# Mouse_STM32F401_DB9.net
KiCad netlist of a schematic drawn in EAGLE
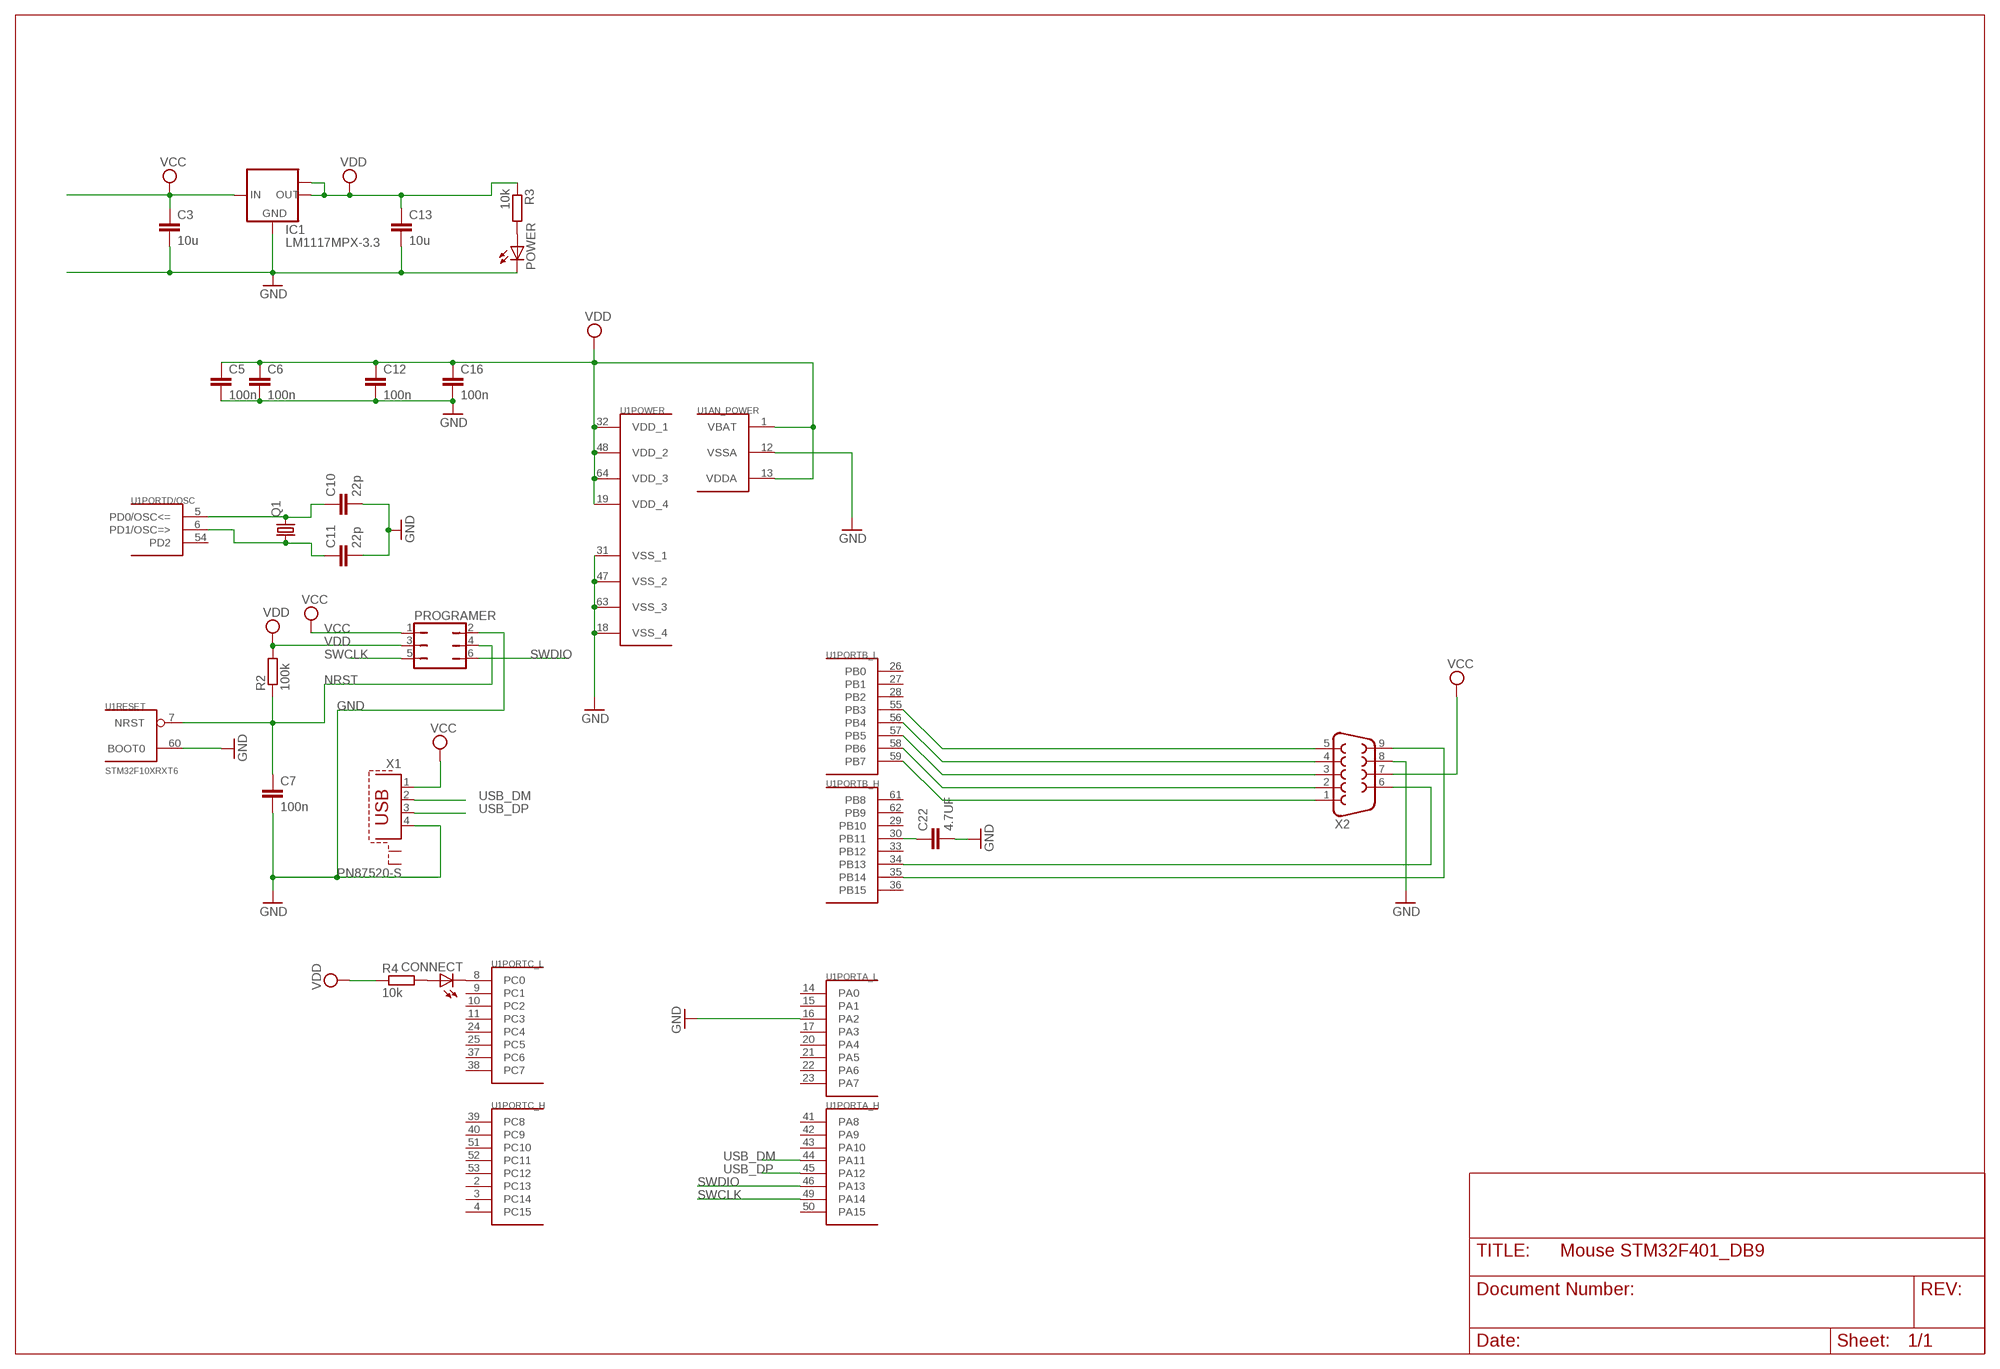
[diagram p0: schematic, sheet 1]

(export (version "E")
  (design (tool "Eeschema 10.0.6"))
  (components
    (comp (ref "C3")
      (value "10u")
      (footprint "eagle-import:C1206")
      (libsource (lib "eagle-import") (part "C-EUC1206"))
    )
    (comp (ref "C5")
      (value "100n")
      (footprint "eagle-import:C0603")
      (libsource (lib "eagle-import") (part "C-EUC0603"))
    )
    (comp (ref "C6")
      (value "100n")
      (footprint "eagle-import:C0603")
      (libsource (lib "eagle-import") (part "C-EUC0603"))
    )
    (comp (ref "C7")
      (value "100n")
      (footprint "eagle-import:C0603")
      (libsource (lib "eagle-import") (part "C-EUC0603"))
    )
    (comp (ref "C10")
      (value "22p")
      (footprint "eagle-import:C0603")
      (libsource (lib "eagle-import") (part "C-EUC0603"))
    )
    (comp (ref "C11")
      (value "22p")
      (footprint "eagle-import:C0603")
      (libsource (lib "eagle-import") (part "C-EUC0603"))
    )
    (comp (ref "C12")
      (value "100n")
      (footprint "eagle-import:C0603")
      (libsource (lib "eagle-import") (part "C-EUC0603"))
    )
    (comp (ref "C13")
      (value "10u")
      (footprint "eagle-import:C1206")
      (libsource (lib "eagle-import") (part "C-EUC1206"))
    )
    (comp (ref "C16")
      (value "100n")
      (footprint "eagle-import:C0603")
      (libsource (lib "eagle-import") (part "C-EUC0603"))
    )
    (comp (ref "C22")
      (value "4.7UF")
      (footprint "eagle-import:C1206")
      (libsource (lib "eagle-import") (part "C-EUC1206"))
    )
    (comp (ref "CONNECT")
      (value "LEDSML0805")
      (footprint "eagle-import:SML0805")
      (libsource (lib "eagle-import") (part "LEDSML0805"))
    )
    (comp (ref "IC1")
      (value "LM1117MPX-3.3")
      (footprint "eagle-import:SOT223")
      (libsource (lib "eagle-import") (part "LM1117MPX-3.3"))
    )
    (comp (ref "POWER")
      (value "LEDSML0805")
      (footprint "eagle-import:SML0805")
      (libsource (lib "eagle-import") (part "LEDSML0805"))
    )
    (comp (ref "PROGRAMER")
      (value "JP3Q")
      (footprint "eagle-import:JP3Q")
      (libsource (lib "eagle-import") (part "JP3Q"))
    )
    (comp (ref "Q1")
      (value "CRYSTALHC49S")
      (footprint "eagle-import:HC49_S")
      (libsource (lib "eagle-import") (part "CRYSTALHC49S"))
    )
    (comp (ref "R2")
      (value "100k")
      (footprint "eagle-import:R0603")
      (libsource (lib "eagle-import") (part "R-EU_R0603"))
    )
    (comp (ref "R3")
      (value "10k")
      (footprint "eagle-import:R0603")
      (libsource (lib "eagle-import") (part "R-EU_R0603"))
    )
    (comp (ref "R4")
      (value "10k")
      (footprint "eagle-import:R0603")
      (libsource (lib "eagle-import") (part "R-EU_R0603"))
    )
    (comp (ref "U1")
      (value "STM32F10XRXT6")
      (footprint "eagle-import:TQFP64")
      (libsource (lib "eagle-import") (part "STM32F10XRXT6"))
    )
    (comp (ref "X1")
      (value "PN87520-S")
      (footprint "eagle-import:PN87520-S")
      (libsource (lib "eagle-import") (part "PN87520-S"))
    )
    (comp (ref "X2")
      (value "F09HP")
      (footprint "eagle-import:F09HP")
      (libsource (lib "eagle-import") (part "F09HP"))
    )
  )
  (nets
    (net (code "1") (name "/NRST") (class "Default")
      (node (ref "C7") (pin "1") (pinfunction "1_1") (pintype "passive"))
      (node (ref "PROGRAMER") (pin "4") (pinfunction "4_4") (pintype "passive"))
      (node (ref "R2") (pin "1") (pinfunction "1_1") (pintype "passive"))
      (node (ref "U1") (pin "7") (pinfunction "NRST_7") (pintype "input"))
    )
    (net (code "2") (name "/SWCLK") (class "Default")
      (node (ref "PROGRAMER") (pin "5") (pinfunction "5_5") (pintype "passive"))
      (node (ref "U1") (pin "49") (pinfunction "PA14_49") (pintype "bidirectional"))
    )
    (net (code "3") (name "/SWDIO") (class "Default")
      (node (ref "PROGRAMER") (pin "6") (pinfunction "6_6") (pintype "passive"))
      (node (ref "U1") (pin "46") (pinfunction "PA13_46") (pintype "bidirectional"))
    )
    (net (code "4") (name "/USB_DM") (class "Default")
      (node (ref "U1") (pin "44") (pinfunction "PA11_44") (pintype "bidirectional"))
      (node (ref "X1") (pin "2") (pinfunction "2_2") (pintype "passive"))
    )
    (net (code "5") (name "/USB_DP") (class "Default")
      (node (ref "U1") (pin "45") (pinfunction "PA12_45") (pintype "bidirectional"))
      (node (ref "X1") (pin "3") (pinfunction "3_3") (pintype "passive"))
    )
    (net (code "6") (name "GND") (class "Default")
      (node (ref "C10") (pin "2") (pinfunction "2_2") (pintype "passive"))
      (node (ref "C11") (pin "2") (pinfunction "2_2") (pintype "passive"))
      (node (ref "C12") (pin "2") (pinfunction "2_2") (pintype "passive"))
      (node (ref "C13") (pin "2") (pinfunction "2_2") (pintype "passive"))
      (node (ref "C16") (pin "2") (pinfunction "2_2") (pintype "passive"))
      (node (ref "C22") (pin "2") (pinfunction "2_2") (pintype "passive"))
      (node (ref "C3") (pin "2") (pinfunction "2_2") (pintype "passive"))
      (node (ref "C5") (pin "2") (pinfunction "2_2") (pintype "passive"))
      (node (ref "C6") (pin "2") (pinfunction "2_2") (pintype "passive"))
      (node (ref "C7") (pin "2") (pinfunction "2_2") (pintype "passive"))
      (node (ref "IC1") (pin "1") (pinfunction "GND_1") (pintype "input"))
      (node (ref "POWER") (pin "C") (pinfunction "C_C") (pintype "passive"))
      (node (ref "PROGRAMER") (pin "2") (pinfunction "2_2") (pintype "passive"))
      (node (ref "U1") (pin "12") (pinfunction "VSSA_12") (pintype "power_in"))
      (node (ref "U1") (pin "16") (pinfunction "PA2_16") (pintype "bidirectional"))
      (node (ref "U1") (pin "18") (pinfunction "VSS_4_18") (pintype "power_in"))
      (node (ref "U1") (pin "31") (pinfunction "VSS_1_31") (pintype "power_in"))
      (node (ref "U1") (pin "47") (pinfunction "VSS_2_47") (pintype "power_in"))
      (node (ref "U1") (pin "60") (pinfunction "BOOT0_60") (pintype "input"))
      (node (ref "U1") (pin "63") (pinfunction "VSS_3_63") (pintype "power_in"))
      (node (ref "X1") (pin "4") (pinfunction "4_4") (pintype "passive"))
      (node (ref "X2") (pin "8") (pinfunction "8_8") (pintype "passive"))
    )
    (net (code "7") (name "Net-(CONNECT-PadA)") (class "Default")
      (node (ref "CONNECT") (pin "A") (pinfunction "A_A") (pintype "passive"))
      (node (ref "R4") (pin "2") (pinfunction "2_2") (pintype "passive"))
    )
    (net (code "8") (name "Net-(POWER-PadA)") (class "Default")
      (node (ref "POWER") (pin "A") (pinfunction "A_A") (pintype "passive"))
      (node (ref "R3") (pin "2") (pinfunction "2_2") (pintype "passive"))
    )
    (net (code "9") (name "Net-(U1D-PB11)") (class "Default")
      (node (ref "C22") (pin "1") (pinfunction "1_1") (pintype "passive"))
      (node (ref "U1") (pin "30") (pinfunction "PB11_30") (pintype "bidirectional"))
    )
    (net (code "10") (name "Net-(U1D-PB13)") (class "Default")
      (node (ref "U1") (pin "34") (pinfunction "PB13_34") (pintype "bidirectional"))
      (node (ref "X2") (pin "6") (pinfunction "6_6") (pintype "passive"))
    )
    (net (code "11") (name "Net-(U1D-PB14)") (class "Default")
      (node (ref "U1") (pin "35") (pinfunction "PB14_35") (pintype "bidirectional"))
      (node (ref "X2") (pin "9") (pinfunction "9_9") (pintype "passive"))
    )
    (net (code "12") (name "Net-(U1E-PB3)") (class "Default")
      (node (ref "U1") (pin "55") (pinfunction "PB3_55") (pintype "bidirectional"))
      (node (ref "X2") (pin "5") (pinfunction "5_5") (pintype "passive"))
    )
    (net (code "13") (name "Net-(U1E-PB4)") (class "Default")
      (node (ref "U1") (pin "56") (pinfunction "PB4_56") (pintype "bidirectional"))
      (node (ref "X2") (pin "4") (pinfunction "4_4") (pintype "passive"))
    )
    (net (code "14") (name "Net-(U1E-PB5)") (class "Default")
      (node (ref "U1") (pin "57") (pinfunction "PB5_57") (pintype "bidirectional"))
      (node (ref "X2") (pin "3") (pinfunction "3_3") (pintype "passive"))
    )
    (net (code "15") (name "Net-(U1E-PB6)") (class "Default")
      (node (ref "U1") (pin "58") (pinfunction "PB6_58") (pintype "bidirectional"))
      (node (ref "X2") (pin "2") (pinfunction "2_2") (pintype "passive"))
    )
    (net (code "16") (name "Net-(U1E-PB7)") (class "Default")
      (node (ref "U1") (pin "59") (pinfunction "PB7_59") (pintype "bidirectional"))
      (node (ref "X2") (pin "1") (pinfunction "1_1") (pintype "passive"))
    )
    (net (code "17") (name "Net-(U1G-PC0)") (class "Default")
      (node (ref "CONNECT") (pin "C") (pinfunction "C_C") (pintype "passive"))
      (node (ref "U1") (pin "8") (pinfunction "PC0_8") (pintype "bidirectional"))
    )
    (net (code "18") (name "Net-(U1H-PD0{slash}OSC<=)") (class "Default")
      (node (ref "C10") (pin "1") (pinfunction "1_1") (pintype "passive"))
      (node (ref "Q1") (pin "2") (pinfunction "2_2") (pintype "passive"))
      (node (ref "U1") (pin "5") (pinfunction "PD0/OSC<=_5") (pintype "bidirectional"))
    )
    (net (code "19") (name "Net-(U1H-PD1{slash}OSC=>)") (class "Default")
      (node (ref "C11") (pin "1") (pinfunction "1_1") (pintype "passive"))
      (node (ref "Q1") (pin "1") (pinfunction "1_1") (pintype "passive"))
      (node (ref "U1") (pin "6") (pinfunction "PD1/OSC=>_6") (pintype "bidirectional"))
    )
    (net (code "20") (name "VCC") (class "Default")
      (node (ref "C3") (pin "1") (pinfunction "1_1") (pintype "passive"))
      (node (ref "IC1") (pin "3") (pinfunction "IN_3") (pintype "input"))
      (node (ref "PROGRAMER") (pin "1") (pinfunction "1_1") (pintype "passive"))
      (node (ref "X1") (pin "1") (pinfunction "1_1") (pintype "passive"))
      (node (ref "X2") (pin "7") (pinfunction "7_7") (pintype "passive"))
    )
    (net (code "21") (name "VDD") (class "Default")
      (node (ref "C12") (pin "1") (pinfunction "1_1") (pintype "passive"))
      (node (ref "C13") (pin "1") (pinfunction "1_1") (pintype "passive"))
      (node (ref "C16") (pin "1") (pinfunction "1_1") (pintype "passive"))
      (node (ref "C5") (pin "1") (pinfunction "1_1") (pintype "passive"))
      (node (ref "C6") (pin "1") (pinfunction "1_1") (pintype "passive"))
      (node (ref "IC1") (pin "2") (pinfunction "OUT_2") (pintype "passive"))
      (node (ref "IC1") (pin "TAB") (pinfunction "OUT1_TAB") (pintype "passive"))
      (node (ref "PROGRAMER") (pin "3") (pinfunction "3_3") (pintype "passive"))
      (node (ref "R2") (pin "2") (pinfunction "2_2") (pintype "passive"))
      (node (ref "R3") (pin "1") (pinfunction "1_1") (pintype "passive"))
      (node (ref "R4") (pin "1") (pinfunction "1_1") (pintype "passive"))
      (node (ref "U1") (pin "1") (pinfunction "VBAT_1") (pintype "power_in"))
      (node (ref "U1") (pin "13") (pinfunction "VDDA_13") (pintype "power_in"))
      (node (ref "U1") (pin "19") (pinfunction "VDD_4_19") (pintype "power_in"))
      (node (ref "U1") (pin "32") (pinfunction "VDD_1_32") (pintype "power_in"))
      (node (ref "U1") (pin "48") (pinfunction "VDD_2_48") (pintype "power_in"))
      (node (ref "U1") (pin "64") (pinfunction "VDD_3_64") (pintype "power_in"))
    )
    (net (code "22") (name "unconnected-(U1B-PA8-Pad41)") (class "Default")
      (node (ref "U1") (pin "41") (pinfunction "PA8_41") (pintype "bidirectional"))
    )
    (net (code "23") (name "unconnected-(U1B-PA9-Pad42)") (class "Default")
      (node (ref "U1") (pin "42") (pinfunction "PA9_42") (pintype "bidirectional"))
    )
    (net (code "24") (name "unconnected-(U1B-PA10-Pad43)") (class "Default")
      (node (ref "U1") (pin "43") (pinfunction "PA10_43") (pintype "bidirectional"))
    )
    (net (code "25") (name "unconnected-(U1B-PA15-Pad50)") (class "Default")
      (node (ref "U1") (pin "50") (pinfunction "PA15_50") (pintype "bidirectional"))
    )
    (net (code "26") (name "unconnected-(U1C-PA0-Pad14)") (class "Default")
      (node (ref "U1") (pin "14") (pinfunction "PA0_14") (pintype "bidirectional"))
    )
    (net (code "27") (name "unconnected-(U1C-PA1-Pad15)") (class "Default")
      (node (ref "U1") (pin "15") (pinfunction "PA1_15") (pintype "bidirectional"))
    )
    (net (code "28") (name "unconnected-(U1C-PA3-Pad17)") (class "Default")
      (node (ref "U1") (pin "17") (pinfunction "PA3_17") (pintype "bidirectional"))
    )
    (net (code "29") (name "unconnected-(U1C-PA4-Pad20)") (class "Default")
      (node (ref "U1") (pin "20") (pinfunction "PA4_20") (pintype "bidirectional"))
    )
    (net (code "30") (name "unconnected-(U1C-PA5-Pad21)") (class "Default")
      (node (ref "U1") (pin "21") (pinfunction "PA5_21") (pintype "bidirectional"))
    )
    (net (code "31") (name "unconnected-(U1C-PA6-Pad22)") (class "Default")
      (node (ref "U1") (pin "22") (pinfunction "PA6_22") (pintype "bidirectional"))
    )
    (net (code "32") (name "unconnected-(U1C-PA7-Pad23)") (class "Default")
      (node (ref "U1") (pin "23") (pinfunction "PA7_23") (pintype "bidirectional"))
    )
    (net (code "33") (name "unconnected-(U1D-PB8-Pad61)") (class "Default")
      (node (ref "U1") (pin "61") (pinfunction "PB8_61") (pintype "bidirectional"))
    )
    (net (code "34") (name "unconnected-(U1D-PB9-Pad62)") (class "Default")
      (node (ref "U1") (pin "62") (pinfunction "PB9_62") (pintype "bidirectional"))
    )
    (net (code "35") (name "unconnected-(U1D-PB10-Pad29)") (class "Default")
      (node (ref "U1") (pin "29") (pinfunction "PB10_29") (pintype "bidirectional"))
    )
    (net (code "36") (name "unconnected-(U1D-PB12-Pad33)") (class "Default")
      (node (ref "U1") (pin "33") (pinfunction "PB12_33") (pintype "bidirectional"))
    )
    (net (code "37") (name "unconnected-(U1D-PB15-Pad36)") (class "Default")
      (node (ref "U1") (pin "36") (pinfunction "PB15_36") (pintype "bidirectional"))
    )
    (net (code "38") (name "unconnected-(U1E-PB0-Pad26)") (class "Default")
      (node (ref "U1") (pin "26") (pinfunction "PB0_26") (pintype "bidirectional"))
    )
    (net (code "39") (name "unconnected-(U1E-PB1-Pad27)") (class "Default")
      (node (ref "U1") (pin "27") (pinfunction "PB1_27") (pintype "bidirectional"))
    )
    (net (code "40") (name "unconnected-(U1E-PB2-Pad28)") (class "Default")
      (node (ref "U1") (pin "28") (pinfunction "PB2_28") (pintype "bidirectional"))
    )
    (net (code "41") (name "unconnected-(U1F-PC8-Pad39)") (class "Default")
      (node (ref "U1") (pin "39") (pinfunction "PC8_39") (pintype "bidirectional"))
    )
    (net (code "42") (name "unconnected-(U1F-PC9-Pad40)") (class "Default")
      (node (ref "U1") (pin "40") (pinfunction "PC9_40") (pintype "bidirectional"))
    )
    (net (code "43") (name "unconnected-(U1F-PC10-Pad51)") (class "Default")
      (node (ref "U1") (pin "51") (pinfunction "PC10_51") (pintype "bidirectional"))
    )
    (net (code "44") (name "unconnected-(U1F-PC11-Pad52)") (class "Default")
      (node (ref "U1") (pin "52") (pinfunction "PC11_52") (pintype "bidirectional"))
    )
    (net (code "45") (name "unconnected-(U1F-PC12-Pad53)") (class "Default")
      (node (ref "U1") (pin "53") (pinfunction "PC12_53") (pintype "bidirectional"))
    )
    (net (code "46") (name "unconnected-(U1F-PC13-Pad2)") (class "Default")
      (node (ref "U1") (pin "2") (pinfunction "PC13_2") (pintype "bidirectional"))
    )
    (net (code "47") (name "unconnected-(U1F-PC14-Pad3)") (class "Default")
      (node (ref "U1") (pin "3") (pinfunction "PC14_3") (pintype "bidirectional"))
    )
    (net (code "48") (name "unconnected-(U1F-PC15-Pad4)") (class "Default")
      (node (ref "U1") (pin "4") (pinfunction "PC15_4") (pintype "bidirectional"))
    )
    (net (code "49") (name "unconnected-(U1G-PC1-Pad9)") (class "Default")
      (node (ref "U1") (pin "9") (pinfunction "PC1_9") (pintype "bidirectional"))
    )
    (net (code "50") (name "unconnected-(U1G-PC2-Pad10)") (class "Default")
      (node (ref "U1") (pin "10") (pinfunction "PC2_10") (pintype "bidirectional"))
    )
    (net (code "51") (name "unconnected-(U1G-PC3-Pad11)") (class "Default")
      (node (ref "U1") (pin "11") (pinfunction "PC3_11") (pintype "bidirectional"))
    )
    (net (code "52") (name "unconnected-(U1G-PC4-Pad24)") (class "Default")
      (node (ref "U1") (pin "24") (pinfunction "PC4_24") (pintype "bidirectional"))
    )
    (net (code "53") (name "unconnected-(U1G-PC5-Pad25)") (class "Default")
      (node (ref "U1") (pin "25") (pinfunction "PC5_25") (pintype "bidirectional"))
    )
    (net (code "54") (name "unconnected-(U1G-PC6-Pad37)") (class "Default")
      (node (ref "U1") (pin "37") (pinfunction "PC6_37") (pintype "bidirectional"))
    )
    (net (code "55") (name "unconnected-(U1G-PC7-Pad38)") (class "Default")
      (node (ref "U1") (pin "38") (pinfunction "PC7_38") (pintype "bidirectional"))
    )
    (net (code "56") (name "unconnected-(U1H-PD2-Pad54)") (class "Default")
      (node (ref "U1") (pin "54") (pinfunction "PD2_54") (pintype "bidirectional"))
    )
    (net (code "57") (name "unconnected-(X1-PadS1)") (class "Default")
      (node (ref "X1") (pin "S1") (pinfunction "S1_S1") (pintype "passive"))
    )
    (net (code "58") (name "unconnected-(X1-PadS2)") (class "Default")
      (node (ref "X1") (pin "S2") (pinfunction "S2_S2") (pintype "passive"))
    )
  )
)
